# Project6_Circuit_Diagrams_1_1.net
KiCad netlist of a schematic drawn in EasyEDA
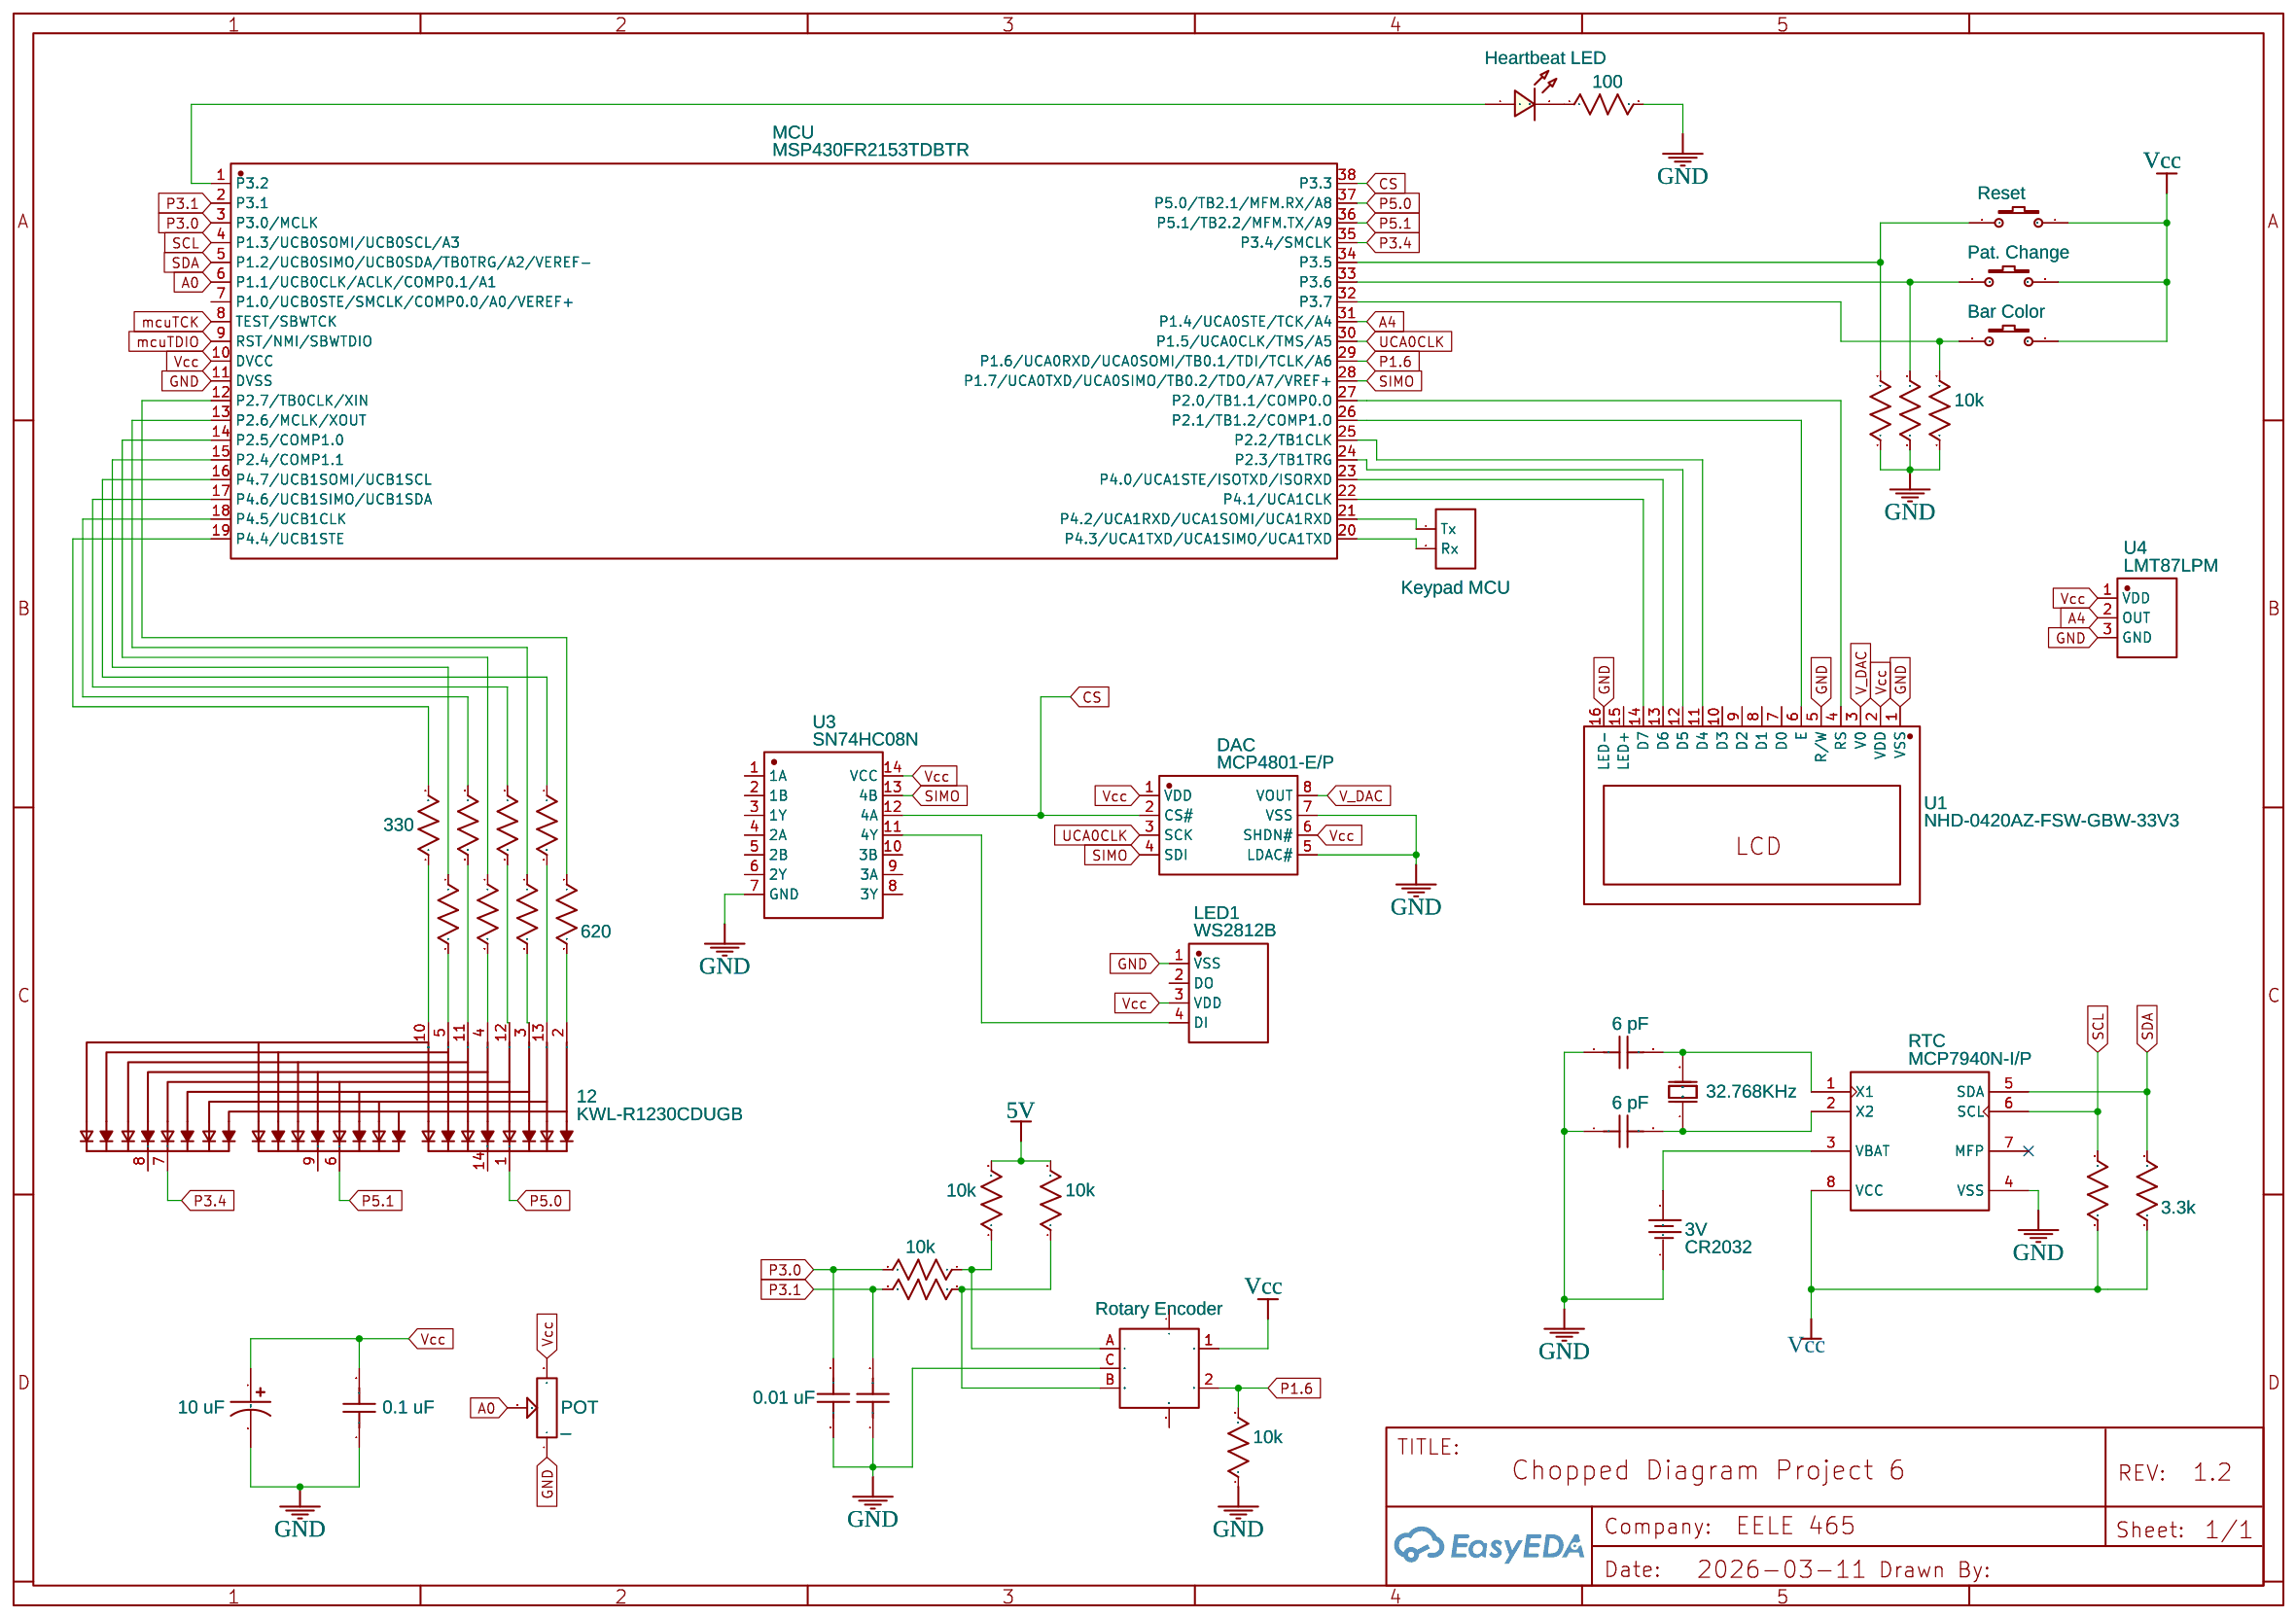
[diagram p0: Main]
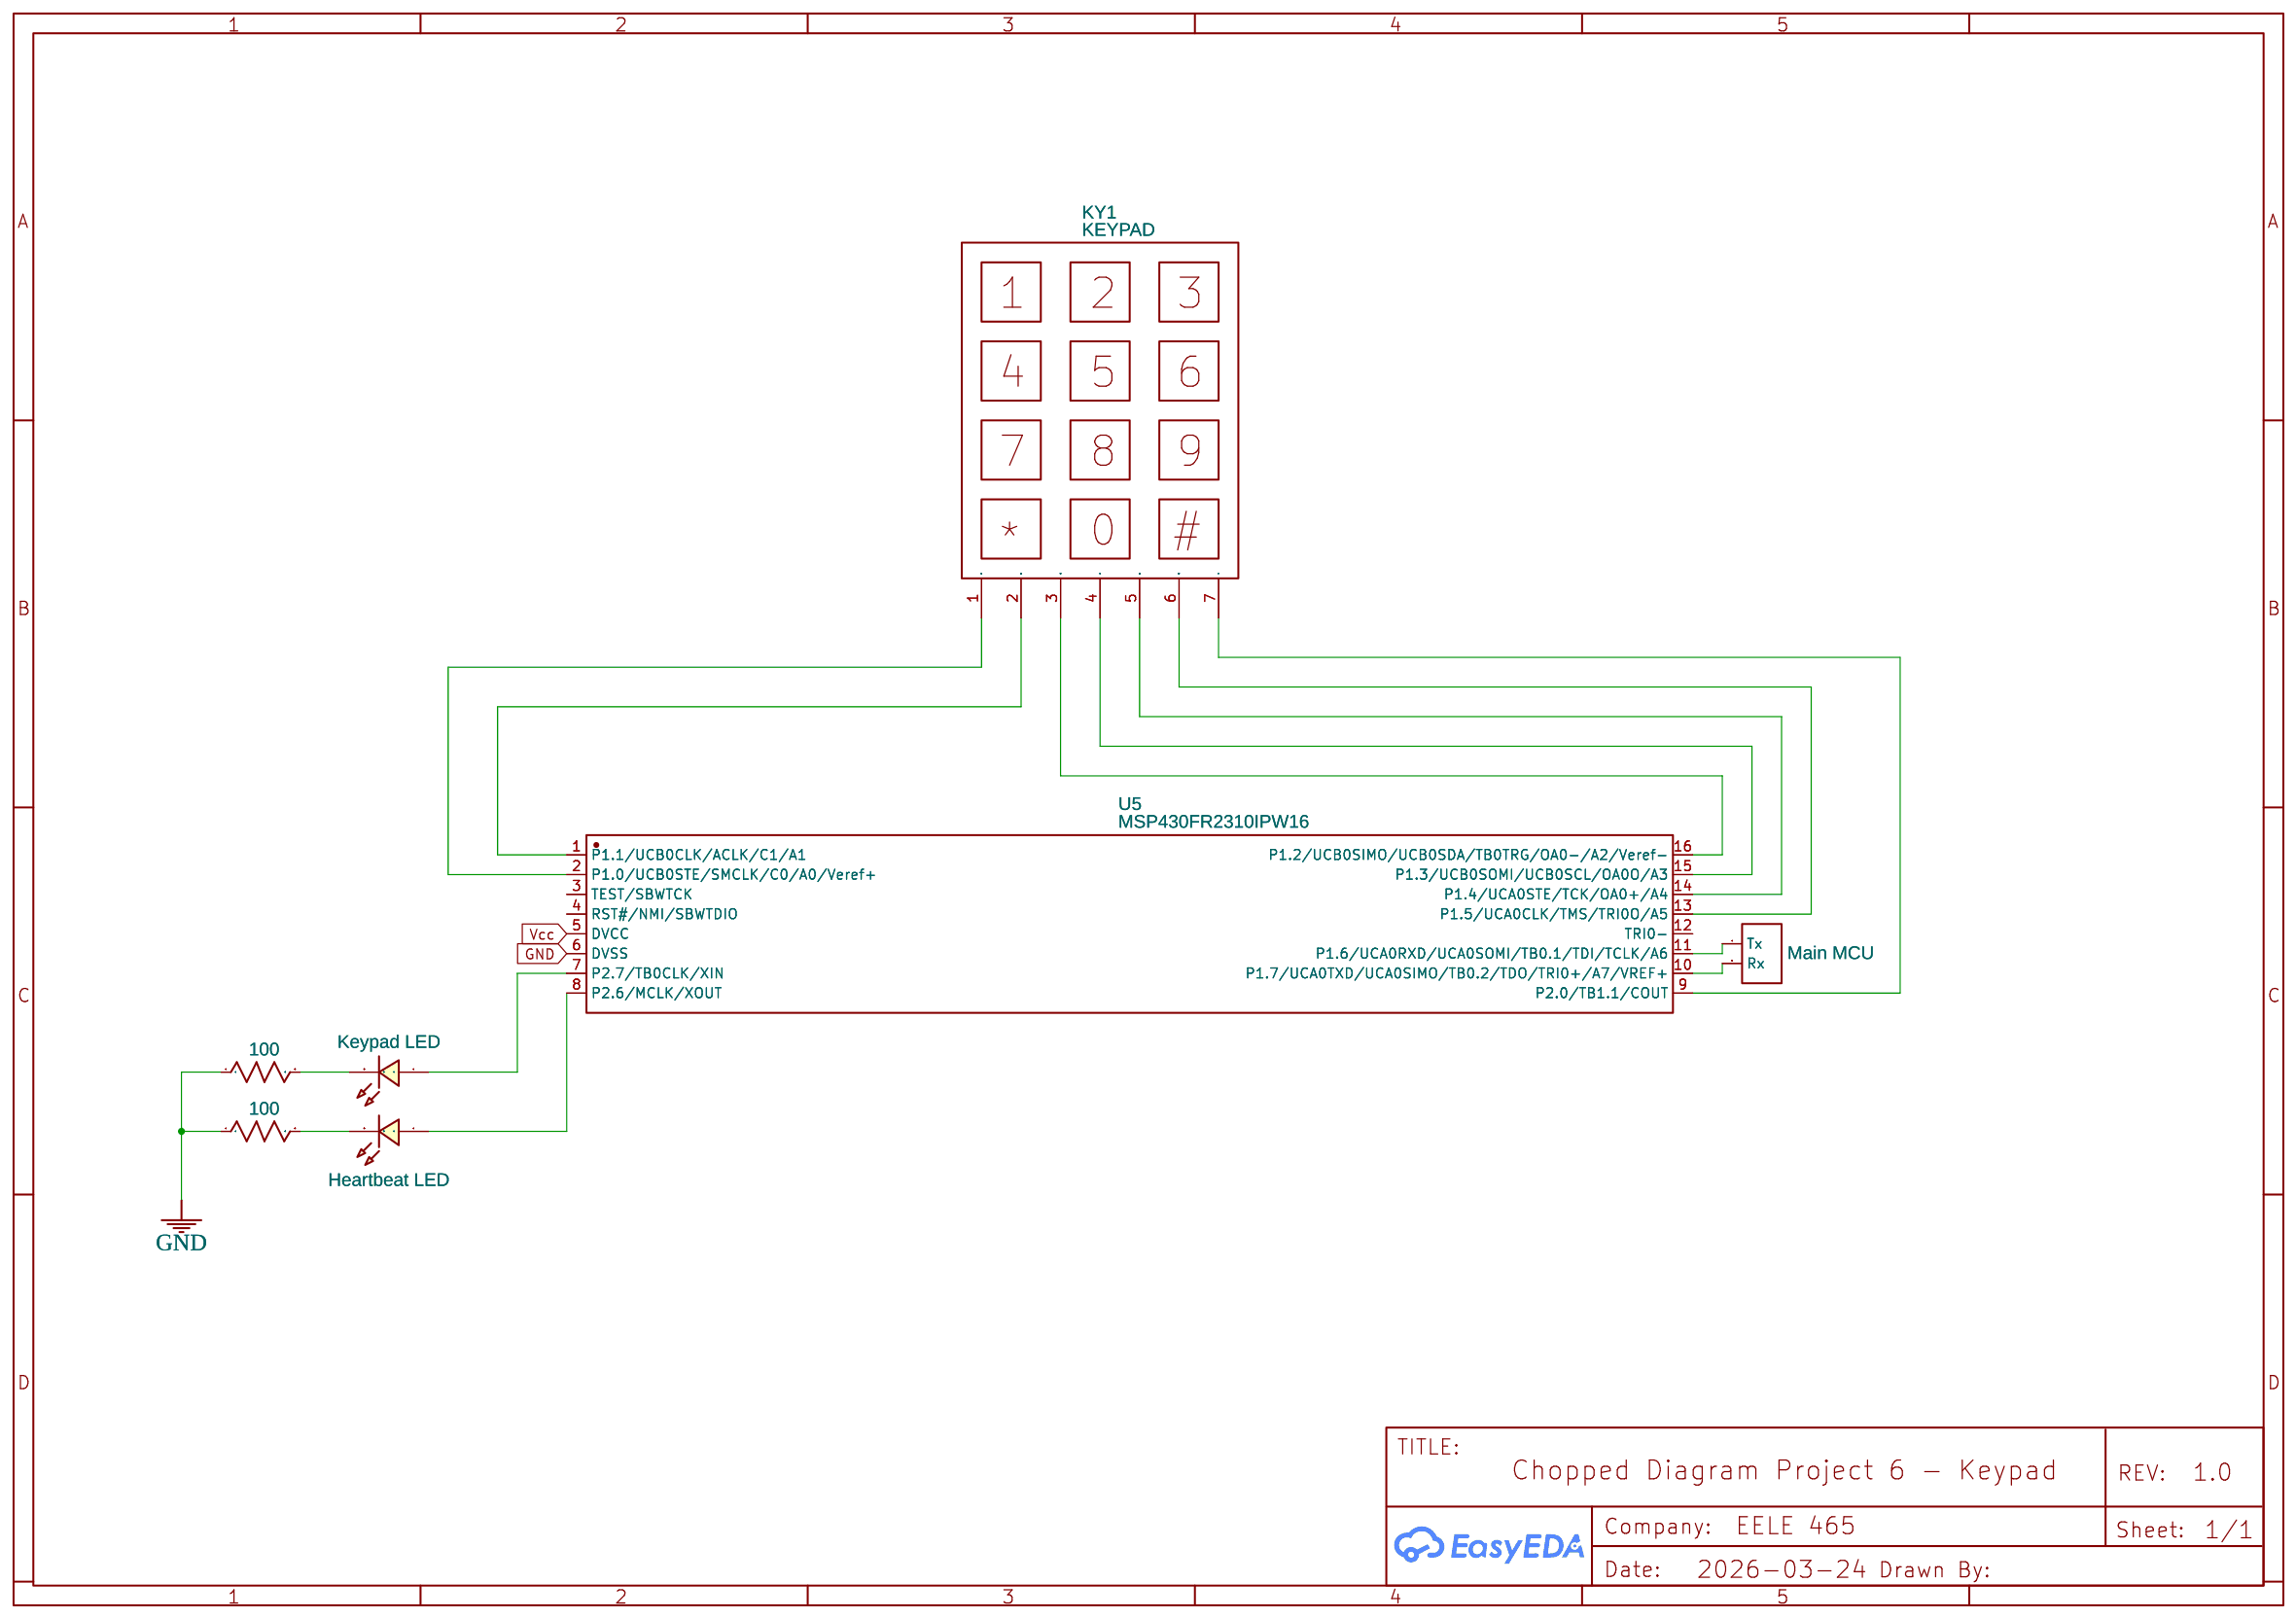
[diagram p1: Keypad]

(export (version "E")
  (design (tool "Eeschema 10.0.6"))
  (components
    (comp (ref "3V")
      (value "CR2032")
      (fields (field (name "Manufacturer Part") "CH25-2032LF") (field (name "Manufacturer") "Multicomp"))
      (libsource (lib "") (part "CH25-2032LF"))
    )
    (comp (ref "12") (value "KWL-R1230CDUGB") (libsource (lib "") (part "KWL-R1230CDUGB")))
    (comp (ref "C1") (value "6 pF") (libsource (lib "") (part "C_0603_US_1")))
    (comp (ref "C2") (value "6 pF") (libsource (lib "") (part "C_0603_US_1")))
    (comp (ref "C3") (value "10 uF") (libsource (lib "") (part "C_Tan_SMD_A_US")))
    (comp (ref "C4") (value "0.1 uF") (libsource (lib "") (part "C_0603_US")))
    (comp (ref "C5") (value "0.01 uF") (libsource (lib "") (part "C_0603_US")))
    (comp (ref "C6") (value "0.01 uF") (libsource (lib "") (part "C_0603_US")))
    (comp (ref "CMD-LINE") (value "Keypad MCU") (libsource (lib "") (part "HDR-F-2.54_1x2")))
    (comp (ref "DAC")
      (value "MCP4801-E/P")
      (fields (field (name "Manufacturer") "MICROCHIP(美国微芯)"))
      (libsource (lib "") (part "MCP4801-E/P"))
    )
    (comp (ref "KEY1")
      (value "Pat. Change")
      (fields (field (name "Manufacturer Part") "K2-1107ST-A4SW-06"))
      (libsource (lib "") (part "K2-3.6×6.1_SMD"))
    )
    (comp (ref "KEY2")
      (value "Reset")
      (fields (field (name "Manufacturer Part") "K2-1107ST-A4SW-06"))
      (libsource (lib "") (part "K2-3.6×6.1_SMD"))
    )
    (comp (ref "KEY3")
      (value "Bar Color")
      (fields (field (name "Manufacturer Part") "K2-1107ST-A4SW-06"))
      (libsource (lib "") (part "K2-3.6×6.1_SMD"))
    )
    (comp (ref "LED1")
      (value "WS2812B")
      (fields (field (name "Manufacturer Part") "WS2812B-4020side-WGYH"))
      (libsource (lib "") (part "WS2812B-4020SIDE-WGYH"))
    )
    (comp (ref "MCU")
      (value "MSP430FR2153TDBTR")
      (fields (field (name "Manufacturer") "TI(德州仪器)"))
      (libsource (lib "") (part "MSP430FR2153TDBTR"))
    )
    (comp (ref "POT") (value "_") (libsource (lib "") (part "SLIDE_POTENTIOMETER_45")))
    (comp (ref "R1") (value "330") (libsource (lib "") (part "R_0603_US")))
    (comp (ref "R2") (value "1k") (libsource (lib "") (part "R_0603_US_2")))
    (comp (ref "R3") (value "1k") (libsource (lib "") (part "R_0603_US_2")))
    (comp (ref "R4") (value "1k") (libsource (lib "") (part "R_0603_US_2")))
    (comp (ref "R5") (value "1k") (libsource (lib "") (part "R_0603_US_2")))
    (comp (ref "R6") (value "1k") (libsource (lib "") (part "R_0603_US_2")))
    (comp (ref "R7") (value "100") (libsource (lib "") (part "R_0603_US_3")))
    (comp (ref "R8") (value "10k") (libsource (lib "") (part "R_0603_US")))
    (comp (ref "R9") (value "330") (libsource (lib "") (part "R_0603_US_2")))
    (comp (ref "R10") (value "620") (libsource (lib "") (part "R_0603_US_2")))
    (comp (ref "R13") (value "10k") (libsource (lib "") (part "R_0603_US")))
    (comp (ref "R14") (value "10k") (libsource (lib "") (part "R_0603_US")))
    (comp (ref "R15") (value "10k") (libsource (lib "") (part "R_0603_US")))
    (comp (ref "R16") (value "10k") (libsource (lib "") (part "R_0603_US")))
    (comp (ref "R17") (value "10k") (libsource (lib "") (part "R_0603_US")))
    (comp (ref "R18") (value "1k") (libsource (lib "") (part "R_0603_US")))
    (comp (ref "R19") (value "3.3k") (libsource (lib "") (part "R_0603_US")))
    (comp (ref "R20") (value "10k") (libsource (lib "") (part "R_0603_US_1")))
    (comp (ref "R21") (value "10k") (libsource (lib "") (part "R_0603_US_1")))
    (comp (ref "RTC")
      (value "MCP7940N-I/P")
      (fields (field (name "Manufacturer") "MICROCHIP(美国微芯)"))
      (libsource (lib "") (part "MCP7940N-I/P"))
    )
    (comp (ref "SC1_ENC")
      (value "Rotary Encoder")
      (fields (field (name "Manufacturer Part") "PEC12R-4130F-S0012") (field (name "Manufacturer") "BOURNS"))
      (libsource (lib "") (part "PEC12R-4130F-S0012"))
    )
    (comp (ref "STATUS1")
      (value "Heartbeat LED")
      (fields
        (field (name "Manufacturer Part") "19-217/GHC-YR1S2/3T")
        (field (name "Manufacturer") "EVERLIGHT(台湾亿光)")
      )
      (libsource (lib "") (part "LED-0603_G"))
    )
    (comp (ref "U1")
      (value "NHD-0420AZ-FSW-GBW-33V3")
      (fields (field (name "Manufacturer") "Newhaven display"))
      (libsource (lib "") (part "NHD-0420AZ-FSW-GBW-33V3"))
    )
    (comp (ref "U3")
      (value "SN74HC08N")
      (fields (field (name "Manufacturer") "TI(德州仪器)"))
      (libsource (lib "") (part "SN74HC08N"))
    )
    (comp (ref "U4")
      (value "LMT87LPM")
      (fields (field (name "Manufacturer") "TI(德州仪器)"))
      (libsource (lib "") (part "LMT87LPM"))
    )
    (comp (ref "X1")
      (value "32.768KHz")
      (fields (field (name "Manufacturer Part") "CFS-20632768EZF"))
      (libsource (lib "") (part "CFS-20632768EZFB"))
    )
    (comp (ref "CMD-LINE1") (value "Main MCU") (libsource (lib "") (part "HDR-F-2.54_1x2")))
    (comp (ref "KY1") (value "KEYPAD") (libsource (lib "") (part "KEYPAD")))
    (comp (ref "R11") (value "100") (libsource (lib "") (part "R_0603_US")))
    (comp (ref "R12") (value "100") (libsource (lib "") (part "R_0603_US")))
    (comp (ref "STATUS2")
      (value "Heartbeat LED")
      (fields
        (field (name "Manufacturer Part") "19-217/GHC-YR1S2/3T")
        (field (name "Manufacturer") "EVERLIGHT(台湾亿光)")
      )
      (libsource (lib "") (part "LED-0603_G"))
    )
    (comp (ref "STATUS3")
      (value "Keypad LED")
      (fields
        (field (name "Manufacturer Part") "19-217/GHC-YR1S2/3T")
        (field (name "Manufacturer") "EVERLIGHT(台湾亿光)")
      )
      (libsource (lib "") (part "LED-0603_G"))
    )
    (comp (ref "U5")
      (value "MSP430FR2310IPW16")
      (fields (field (name "Manufacturer") "TI(德州仪器)"))
      (libsource (lib "") (part "MSP430FR2310IPW16"))
    )
  )
  (nets
    (net (code "1") (name "5V") (class "Default")
      (node (ref "R16") (pin "2") (pinfunction "2_2") (pintype "unspecified"))
      (node (ref "R17") (pin "2") (pinfunction "2_2") (pintype "unspecified"))
    )
    (net (code "2") (name "A0") (class "Default")
      (node (ref "MCU") (pin "6") (pinfunction "P1.1/UCB0CLK/ACLK/COMP0.1/A1_6") (pintype "unspecified"))
      (node (ref "POT") (pin "B") (pinfunction "B_B") (pintype "unspecified"))
    )
    (net (code "3") (name "A4") (class "Default")
      (node (ref "MCU") (pin "31") (pinfunction "P1.4/UCA0STE/TCK/A4_31") (pintype "unspecified"))
      (node (ref "U4") (pin "2") (pinfunction "OUT_2") (pintype "unspecified"))
    )
    (net (code "4") (name "CS") (class "Default")
      (node (ref "DAC") (pin "2") (pinfunction "CS#_2") (pintype "unspecified"))
      (node (ref "MCU") (pin "38") (pinfunction "P3.3_38") (pintype "unspecified"))
      (node (ref "U3") (pin "12") (pinfunction "4A_12") (pintype "unspecified"))
    )
    (net (code "5") (name "GND") (class "Default")
      (node (ref "3V") (pin "1") (pinfunction "1_1") (pintype "input"))
      (node (ref "C1") (pin "1") (pinfunction "1_1") (pintype "unspecified"))
      (node (ref "C2") (pin "1") (pinfunction "1_1") (pintype "unspecified"))
      (node (ref "C3") (pin "2") (pinfunction "2_2") (pintype "unspecified"))
      (node (ref "C4") (pin "1") (pinfunction "1_1") (pintype "unspecified"))
      (node (ref "C5") (pin "1") (pinfunction "1_1") (pintype "unspecified"))
      (node (ref "C6") (pin "1") (pinfunction "1_1") (pintype "unspecified"))
      (node (ref "DAC") (pin "5") (pinfunction "LDAC#_5") (pintype "unspecified"))
      (node (ref "DAC") (pin "7") (pinfunction "VSS_7") (pintype "unspecified"))
      (node (ref "LED1") (pin "1") (pinfunction "VSS_1") (pintype "unspecified"))
      (node (ref "MCU") (pin "11") (pinfunction "DVSS_11") (pintype "unspecified"))
      (node (ref "POT") (pin "A") (pinfunction "A_A") (pintype "unspecified"))
      (node (ref "R11") (pin "1") (pinfunction "1_1") (pintype "unspecified"))
      (node (ref "R12") (pin "1") (pinfunction "1_1") (pintype "unspecified"))
      (node (ref "R13") (pin "1") (pinfunction "1_1") (pintype "unspecified"))
      (node (ref "R14") (pin "1") (pinfunction "1_1") (pintype "unspecified"))
      (node (ref "R15") (pin "1") (pinfunction "1_1") (pintype "unspecified"))
      (node (ref "R7") (pin "2") (pinfunction "2_2") (pintype "unspecified"))
      (node (ref "R8") (pin "1") (pinfunction "1_1") (pintype "unspecified"))
      (node (ref "RTC") (pin "4") (pinfunction "VSS_4") (pintype "passive"))
      (node (ref "SC1_ENC") (pin "C") (pinfunction "C_C") (pintype "unspecified"))
      (node (ref "U1") (pin "1") (pinfunction "VSS_1") (pintype "unspecified"))
      (node (ref "U1") (pin "16") (pinfunction "LED-_16") (pintype "unspecified"))
      (node (ref "U1") (pin "5") (pinfunction "R/W_5") (pintype "unspecified"))
      (node (ref "U3") (pin "7") (pinfunction "GND_7") (pintype "unspecified"))
      (node (ref "U4") (pin "3") (pinfunction "GND_3") (pintype "unspecified"))
      (node (ref "U5") (pin "6") (pinfunction "DVSS_6") (pintype "unspecified"))
    )
    (net (code "6") (name "Net-(12-Pad2)") (class "Default")
      (node (ref "12") (pin "2") (pinfunction "2_2") (pintype "unspecified"))
      (node (ref "R10") (pin "2") (pinfunction "2_2") (pintype "unspecified"))
    )
    (net (code "7") (name "Net-(12-Pad3)") (class "Default")
      (node (ref "12") (pin "3") (pinfunction "3_3") (pintype "unspecified"))
      (node (ref "R6") (pin "2") (pinfunction "2_2") (pintype "unspecified"))
    )
    (net (code "8") (name "Net-(12-Pad4)") (class "Default")
      (node (ref "12") (pin "4") (pinfunction "4_4") (pintype "unspecified"))
      (node (ref "R4") (pin "2") (pinfunction "2_2") (pintype "unspecified"))
    )
    (net (code "9") (name "Net-(12-Pad5)") (class "Default")
      (node (ref "12") (pin "5") (pinfunction "5_5") (pintype "unspecified"))
      (node (ref "R2") (pin "2") (pinfunction "2_2") (pintype "unspecified"))
    )
    (net (code "10") (name "Net-(12-Pad10)") (class "Default")
      (node (ref "12") (pin "10") (pinfunction "10_10") (pintype "unspecified"))
      (node (ref "R1") (pin "1") (pinfunction "1_1") (pintype "unspecified"))
    )
    (net (code "11") (name "Net-(12-Pad11)") (class "Default")
      (node (ref "12") (pin "11") (pinfunction "11_11") (pintype "unspecified"))
      (node (ref "R3") (pin "2") (pinfunction "2_2") (pintype "unspecified"))
    )
    (net (code "12") (name "Net-(12-Pad12)") (class "Default")
      (node (ref "12") (pin "12") (pinfunction "12_12") (pintype "unspecified"))
      (node (ref "R5") (pin "2") (pinfunction "2_2") (pintype "unspecified"))
    )
    (net (code "13") (name "Net-(12-Pad13)") (class "Default")
      (node (ref "12") (pin "13") (pinfunction "13_13") (pintype "unspecified"))
      (node (ref "R9") (pin "2") (pinfunction "2_2") (pintype "unspecified"))
    )
    (net (code "14") (name "Net-(CMD-LINE-Rx)") (class "Default")
      (node (ref "CMD-LINE") (pin "2") (pinfunction "Rx_2") (pintype "input"))
      (node (ref "MCU") (pin "20") (pinfunction "P4.3/UCA1TXD/UCA1SIMO/UCA1TXD_20") (pintype "unspecified"))
    )
    (net (code "15") (name "Net-(CMD-LINE-Tx)") (class "Default")
      (node (ref "CMD-LINE") (pin "1") (pinfunction "Tx_1") (pintype "input"))
      (node (ref "MCU") (pin "21") (pinfunction "P4.2/UCA1RXD/UCA1SOMI/UCA1RXD_21") (pintype "unspecified"))
    )
    (net (code "16") (name "Net-(CMD-LINE1-Rx)") (class "Default")
      (node (ref "CMD-LINE1") (pin "2") (pinfunction "Rx_2") (pintype "input"))
      (node (ref "U5") (pin "10") (pinfunction "P1.7/UCA0TXD/UCA0SIMO/TB0.2/TDO/TRI0+/A7/VREF+_10") (pintype "unspecified"))
    )
    (net (code "17") (name "Net-(CMD-LINE1-Tx)") (class "Default")
      (node (ref "CMD-LINE1") (pin "1") (pinfunction "Tx_1") (pintype "input"))
      (node (ref "U5") (pin "11") (pinfunction "P1.6/UCA0RXD/UCA0SOMI/TB0.1/TDI/TCLK/A6_11") (pintype "unspecified"))
    )
    (net (code "18") (name "Net-(LED1-DI)") (class "Default")
      (node (ref "LED1") (pin "4") (pinfunction "DI_4") (pintype "unspecified"))
      (node (ref "U3") (pin "11") (pinfunction "4Y_11") (pintype "unspecified"))
    )
    (net (code "19") (name "Net-(MCU-P2.0{slash}TB1.1{slash}COMP0.O)") (class "Default")
      (node (ref "MCU") (pin "27") (pinfunction "P2.0/TB1.1/COMP0.O_27") (pintype "unspecified"))
      (node (ref "U1") (pin "4") (pinfunction "RS_4") (pintype "unspecified"))
    )
    (net (code "20") (name "Net-(MCU-P2.1{slash}TB1.2{slash}COMP1.O)") (class "Default")
      (node (ref "MCU") (pin "26") (pinfunction "P2.1/TB1.2/COMP1.O_26") (pintype "unspecified"))
      (node (ref "U1") (pin "6") (pinfunction "E_6") (pintype "unspecified"))
    )
    (net (code "21") (name "Net-(MCU-P2.2{slash}TB1CLK)") (class "Default")
      (node (ref "MCU") (pin "25") (pinfunction "P2.2/TB1CLK_25") (pintype "unspecified"))
      (node (ref "U1") (pin "11") (pinfunction "D4_11") (pintype "unspecified"))
    )
    (net (code "22") (name "Net-(MCU-P2.3{slash}TB1TRG)") (class "Default")
      (node (ref "MCU") (pin "24") (pinfunction "P2.3/TB1TRG_24") (pintype "unspecified"))
      (node (ref "U1") (pin "12") (pinfunction "D5_12") (pintype "unspecified"))
    )
    (net (code "23") (name "Net-(MCU-P2.4{slash}COMP1.1)") (class "Default")
      (node (ref "MCU") (pin "15") (pinfunction "P2.4/COMP1.1_15") (pintype "unspecified"))
      (node (ref "R2") (pin "1") (pinfunction "1_1") (pintype "unspecified"))
    )
    (net (code "24") (name "Net-(MCU-P2.5{slash}COMP1.0)") (class "Default")
      (node (ref "MCU") (pin "14") (pinfunction "P2.5/COMP1.0_14") (pintype "unspecified"))
      (node (ref "R4") (pin "1") (pinfunction "1_1") (pintype "unspecified"))
    )
    (net (code "25") (name "Net-(MCU-P2.6{slash}MCLK{slash}XOUT)") (class "Default")
      (node (ref "MCU") (pin "13") (pinfunction "P2.6/MCLK/XOUT_13") (pintype "unspecified"))
      (node (ref "R6") (pin "1") (pinfunction "1_1") (pintype "unspecified"))
    )
    (net (code "26") (name "Net-(MCU-P2.7{slash}TB0CLK{slash}XIN)") (class "Default")
      (node (ref "MCU") (pin "12") (pinfunction "P2.7/TB0CLK/XIN_12") (pintype "unspecified"))
      (node (ref "R10") (pin "1") (pinfunction "1_1") (pintype "unspecified"))
    )
    (net (code "27") (name "Net-(MCU-P3.2)") (class "Default")
      (node (ref "MCU") (pin "1") (pinfunction "P3.2_1") (pintype "unspecified"))
      (node (ref "STATUS1") (pin "1") (pinfunction "1_1") (pintype "unspecified"))
    )
    (net (code "28") (name "Net-(MCU-P3.5)") (class "Default")
      (node (ref "KEY2") (pin "1") (pinfunction "1_1") (pintype "unspecified"))
      (node (ref "MCU") (pin "34") (pinfunction "P3.5_34") (pintype "unspecified"))
      (node (ref "R14") (pin "2") (pinfunction "2_2") (pintype "unspecified"))
    )
    (net (code "29") (name "Net-(MCU-P3.6)") (class "Default")
      (node (ref "KEY1") (pin "1") (pinfunction "1_1") (pintype "unspecified"))
      (node (ref "MCU") (pin "33") (pinfunction "P3.6_33") (pintype "unspecified"))
      (node (ref "R13") (pin "2") (pinfunction "2_2") (pintype "unspecified"))
    )
    (net (code "30") (name "Net-(MCU-P3.7)") (class "Default")
      (node (ref "KEY3") (pin "1") (pinfunction "1_1") (pintype "unspecified"))
      (node (ref "MCU") (pin "32") (pinfunction "P3.7_32") (pintype "unspecified"))
      (node (ref "R8") (pin "2") (pinfunction "2_2") (pintype "unspecified"))
    )
    (net (code "31") (name "Net-(MCU-P4.0{slash}UCA1STE{slash}ISOTXD{slash}ISORXD)") (class "Default")
      (node (ref "MCU") (pin "23") (pinfunction "P4.0/UCA1STE/ISOTXD/ISORXD_23") (pintype "unspecified"))
      (node (ref "U1") (pin "13") (pinfunction "D6_13") (pintype "unspecified"))
    )
    (net (code "32") (name "Net-(MCU-P4.1{slash}UCA1CLK)") (class "Default")
      (node (ref "MCU") (pin "22") (pinfunction "P4.1/UCA1CLK_22") (pintype "unspecified"))
      (node (ref "U1") (pin "14") (pinfunction "D7_14") (pintype "unspecified"))
    )
    (net (code "33") (name "Net-(MCU-P4.4{slash}UCB1STE)") (class "Default")
      (node (ref "MCU") (pin "19") (pinfunction "P4.4/UCB1STE_19") (pintype "unspecified"))
      (node (ref "R1") (pin "2") (pinfunction "2_2") (pintype "unspecified"))
    )
    (net (code "34") (name "Net-(MCU-P4.5{slash}UCB1CLK)") (class "Default")
      (node (ref "MCU") (pin "18") (pinfunction "P4.5/UCB1CLK_18") (pintype "unspecified"))
      (node (ref "R3") (pin "1") (pinfunction "1_1") (pintype "unspecified"))
    )
    (net (code "35") (name "Net-(MCU-P4.6{slash}UCB1SIMO{slash}UCB1SDA)") (class "Default")
      (node (ref "MCU") (pin "17") (pinfunction "P4.6/UCB1SIMO/UCB1SDA_17") (pintype "unspecified"))
      (node (ref "R5") (pin "1") (pinfunction "1_1") (pintype "unspecified"))
    )
    (net (code "36") (name "Net-(MCU-P4.7{slash}UCB1SOMI{slash}UCB1SCL)") (class "Default")
      (node (ref "MCU") (pin "16") (pinfunction "P4.7/UCB1SOMI/UCB1SCL_16") (pintype "unspecified"))
      (node (ref "R9") (pin "1") (pinfunction "1_1") (pintype "unspecified"))
    )
    (net (code "37") (name "Net-(R7-Pad1)") (class "Default")
      (node (ref "R7") (pin "1") (pinfunction "1_1") (pintype "unspecified"))
      (node (ref "STATUS1") (pin "2") (pinfunction "2_2") (pintype "unspecified"))
    )
    (net (code "38") (name "Net-(R11-Pad2)") (class "Default")
      (node (ref "R11") (pin "2") (pinfunction "2_2") (pintype "unspecified"))
      (node (ref "STATUS3") (pin "2") (pinfunction "2_2") (pintype "unspecified"))
    )
    (net (code "39") (name "Net-(R12-Pad2)") (class "Default")
      (node (ref "R12") (pin "2") (pinfunction "2_2") (pintype "unspecified"))
      (node (ref "STATUS2") (pin "2") (pinfunction "2_2") (pintype "unspecified"))
    )
    (net (code "40") (name "Net-(R16-Pad1)") (class "Default")
      (node (ref "R16") (pin "1") (pinfunction "1_1") (pintype "unspecified"))
      (node (ref "R20") (pin "1") (pinfunction "1_1") (pintype "unspecified"))
      (node (ref "SC1_ENC") (pin "A") (pinfunction "A_A") (pintype "unspecified"))
    )
    (net (code "41") (name "Net-(R17-Pad1)") (class "Default")
      (node (ref "R17") (pin "1") (pinfunction "1_1") (pintype "unspecified"))
      (node (ref "R21") (pin "1") (pinfunction "1_1") (pintype "unspecified"))
      (node (ref "SC1_ENC") (pin "B") (pinfunction "B_B") (pintype "unspecified"))
    )
    (net (code "42") (name "Net-(RTC-VBAT)") (class "Default")
      (node (ref "3V") (pin "2") (pinfunction "2_2") (pintype "input"))
      (node (ref "RTC") (pin "3") (pinfunction "VBAT_3") (pintype "passive"))
    )
    (net (code "43") (name "Net-(RTC-X1)") (class "Default")
      (node (ref "C1") (pin "2") (pinfunction "2_2") (pintype "unspecified"))
      (node (ref "RTC") (pin "1") (pinfunction "X1_1") (pintype "unspecified"))
      (node (ref "X1") (pin "2") (pinfunction "OSC2_2") (pintype "input"))
    )
    (net (code "44") (name "Net-(RTC-X2)") (class "Default")
      (node (ref "C2") (pin "2") (pinfunction "2_2") (pintype "unspecified"))
      (node (ref "RTC") (pin "2") (pinfunction "X2_2") (pintype "output"))
      (node (ref "X1") (pin "1") (pinfunction "OSC1_1") (pintype "input"))
    )
    (net (code "45") (name "Net-(U5-P1.0{slash}UCB0STE{slash}SMCLK{slash}C0{slash}A0{slash}Veref+)") (class "Default")
      (node (ref "KY1") (pin "1") (pinfunction "1_1") (pintype "unspecified"))
      (node (ref "U5") (pin "2") (pinfunction "P1.0/UCB0STE/SMCLK/C0/A0/Veref+_2") (pintype "unspecified"))
    )
    (net (code "46") (name "Net-(U5-P1.1{slash}UCB0CLK{slash}ACLK{slash}C1{slash}A1)") (class "Default")
      (node (ref "KY1") (pin "2") (pinfunction "2_2") (pintype "unspecified"))
      (node (ref "U5") (pin "1") (pinfunction "P1.1/UCB0CLK/ACLK/C1/A1_1") (pintype "unspecified"))
    )
    (net (code "47") (name "Net-(U5-P1.2{slash}UCB0SIMO{slash}UCB0SDA{slash}TB0TRG{slash}OA0-{slash}A2{slash}Veref-)") (class "Default")
      (node (ref "KY1") (pin "3") (pinfunction "3_3") (pintype "unspecified"))
      (node (ref "U5") (pin "16") (pinfunction "P1.2/UCB0SIMO/UCB0SDA/TB0TRG/OA0-/A2/Veref-_16") (pintype "unspecified"))
    )
    (net (code "48") (name "Net-(U5-P1.3{slash}UCB0SOMI{slash}UCB0SCL{slash}OA0O{slash}A3)") (class "Default")
      (node (ref "KY1") (pin "4") (pinfunction "4_4") (pintype "unspecified"))
      (node (ref "U5") (pin "15") (pinfunction "P1.3/UCB0SOMI/UCB0SCL/OA0O/A3_15") (pintype "unspecified"))
    )
    (net (code "49") (name "Net-(U5-P1.4{slash}UCA0STE{slash}TCK{slash}OA0+{slash}A4)") (class "Default")
      (node (ref "KY1") (pin "5") (pinfunction "5_5") (pintype "unspecified"))
      (node (ref "U5") (pin "14") (pinfunction "P1.4/UCA0STE/TCK/OA0+/A4_14") (pintype "unspecified"))
    )
    (net (code "50") (name "Net-(U5-P1.5{slash}UCA0CLK{slash}TMS{slash}TRI0O{slash}A5)") (class "Default")
      (node (ref "KY1") (pin "6") (pinfunction "6_6") (pintype "unspecified"))
      (node (ref "U5") (pin "13") (pinfunction "P1.5/UCA0CLK/TMS/TRI0O/A5_13") (pintype "unspecified"))
    )
    (net (code "51") (name "Net-(U5-P2.0{slash}TB1.1{slash}COUT)") (class "Default")
      (node (ref "KY1") (pin "7") (pinfunction "7_7") (pintype "unspecified"))
      (node (ref "U5") (pin "9") (pinfunction "P2.0/TB1.1/COUT_9") (pintype "unspecified"))
    )
    (net (code "52") (name "Net-(U5-P2.6{slash}MCLK{slash}XOUT)") (class "Default")
      (node (ref "STATUS2") (pin "1") (pinfunction "1_1") (pintype "unspecified"))
      (node (ref "U5") (pin "8") (pinfunction "P2.6/MCLK/XOUT_8") (pintype "unspecified"))
    )
    (net (code "53") (name "Net-(U5-P2.7{slash}TB0CLK{slash}XIN)") (class "Default")
      (node (ref "STATUS3") (pin "1") (pinfunction "1_1") (pintype "unspecified"))
      (node (ref "U5") (pin "7") (pinfunction "P2.7/TB0CLK/XIN_7") (pintype "unspecified"))
    )
    (net (code "54") (name "P1.6") (class "Default")
      (node (ref "MCU") (pin "29") (pinfunction "P1.6/UCA0RXD/UCA0SOMI/TB0.1/TDI/TCLK/A6_29") (pintype "unspecified"))
      (node (ref "R15") (pin "2") (pinfunction "2_2") (pintype "unspecified"))
      (node (ref "SC1_ENC") (pin "2") (pinfunction "2_2") (pintype "unspecified"))
    )
    (net (code "55") (name "P3.0") (class "Default")
      (node (ref "C5") (pin "2") (pinfunction "2_2") (pintype "unspecified"))
      (node (ref "MCU") (pin "3") (pinfunction "P3.0/MCLK_3") (pintype "unspecified"))
      (node (ref "R20") (pin "2") (pinfunction "2_2") (pintype "unspecified"))
    )
    (net (code "56") (name "P3.1") (class "Default")
      (node (ref "C6") (pin "2") (pinfunction "2_2") (pintype "unspecified"))
      (node (ref "MCU") (pin "2") (pinfunction "P3.1_2") (pintype "unspecified"))
      (node (ref "R21") (pin "2") (pinfunction "2_2") (pintype "unspecified"))
    )
    (net (code "57") (name "P3.4") (class "Default")
      (node (ref "12") (pin "7") (pinfunction "7_7") (pintype "unspecified"))
      (node (ref "MCU") (pin "35") (pinfunction "P3.4/SMCLK_35") (pintype "unspecified"))
    )
    (net (code "58") (name "P5.0") (class "Default")
      (node (ref "12") (pin "1") (pinfunction "1_1") (pintype "unspecified"))
      (node (ref "MCU") (pin "37") (pinfunction "P5.0/TB2.1/MFM.RX/A8_37") (pintype "unspecified"))
    )
    (net (code "59") (name "P5.1") (class "Default")
      (node (ref "12") (pin "6") (pinfunction "6_6") (pintype "unspecified"))
      (node (ref "MCU") (pin "36") (pinfunction "P5.1/TB2.2/MFM.TX/A9_36") (pintype "unspecified"))
    )
    (net (code "60") (name "SCL") (class "Default")
      (node (ref "MCU") (pin "4") (pinfunction "P1.3/UCB0SOMI/UCB0SCL/A3_4") (pintype "unspecified"))
      (node (ref "R18") (pin "2") (pinfunction "2_2") (pintype "unspecified"))
      (node (ref "RTC") (pin "6") (pinfunction "SCL_6") (pintype "unspecified"))
    )
    (net (code "61") (name "SDA") (class "Default")
      (node (ref "MCU") (pin "5") (pinfunction "P1.2/UCB0SIMO/UCB0SDA/TB0TRG/A2/VEREF-_5") (pintype "unspecified"))
      (node (ref "R19") (pin "2") (pinfunction "2_2") (pintype "unspecified"))
      (node (ref "RTC") (pin "5") (pinfunction "SDA_5") (pintype "bidirectional"))
    )
    (net (code "62") (name "SIMO") (class "Default")
      (node (ref "DAC") (pin "4") (pinfunction "SDI_4") (pintype "unspecified"))
      (node (ref "MCU") (pin "28") (pinfunction "P1.7/UCA0TXD/UCA0SIMO/TB0.2/TDO/A7/VREF+_28") (pintype "unspecified"))
      (node (ref "U3") (pin "13") (pinfunction "4B_13") (pintype "unspecified"))
    )
    (net (code "63") (name "UCA0CLK") (class "Default")
      (node (ref "DAC") (pin "3") (pinfunction "SCK_3") (pintype "unspecified"))
      (node (ref "MCU") (pin "30") (pinfunction "P1.5/UCA0CLK/TMS/A5_30") (pintype "unspecified"))
    )
    (net (code "64") (name "V_DAC") (class "Default")
      (node (ref "DAC") (pin "8") (pinfunction "VOUT_8") (pintype "unspecified"))
      (node (ref "U1") (pin "3") (pinfunction "V0_3") (pintype "unspecified"))
    )
    (net (code "65") (name "Vcc") (class "Default")
      (node (ref "C3") (pin "1") (pinfunction "1_1") (pintype "unspecified"))
      (node (ref "C4") (pin "2") (pinfunction "2_2") (pintype "unspecified"))
      (node (ref "DAC") (pin "1") (pinfunction "VDD_1") (pintype "unspecified"))
      (node (ref "DAC") (pin "6") (pinfunction "SHDN#_6") (pintype "unspecified"))
      (node (ref "KEY1") (pin "2") (pinfunction "2_2") (pintype "unspecified"))
      (node (ref "KEY2") (pin "2") (pinfunction "2_2") (pintype "unspecified"))
      (node (ref "KEY3") (pin "2") (pinfunction "2_2") (pintype "unspecified"))
      (node (ref "LED1") (pin "3") (pinfunction "VDD_3") (pintype "unspecified"))
      (node (ref "MCU") (pin "10") (pinfunction "DVCC_10") (pintype "unspecified"))
      (node (ref "POT") (pin "D") (pinfunction "C_D") (pintype "unspecified"))
      (node (ref "R18") (pin "1") (pinfunction "1_1") (pintype "unspecified"))
      (node (ref "R19") (pin "1") (pinfunction "1_1") (pintype "unspecified"))
      (node (ref "RTC") (pin "8") (pinfunction "VCC_8") (pintype "passive"))
      (node (ref "SC1_ENC") (pin "1") (pinfunction "1_1") (pintype "unspecified"))
      (node (ref "U1") (pin "2") (pinfunction "VDD_2") (pintype "unspecified"))
      (node (ref "U3") (pin "14") (pinfunction "VCC_14") (pintype "unspecified"))
      (node (ref "U4") (pin "1") (pinfunction "VDD_1") (pintype "unspecified"))
      (node (ref "U5") (pin "5") (pinfunction "DVCC_5") (pintype "unspecified"))
    )
    (net (code "66") (name "mcuTCK") (class "Default")
      (node (ref "MCU") (pin "8") (pinfunction "TEST/SBWTCK_8") (pintype "unspecified"))
    )
    (net (code "67") (name "mcuTDIO") (class "Default")
      (node (ref "MCU") (pin "9") (pinfunction "RST/NMI/SBWTDIO_9") (pintype "unspecified"))
    )
    (net (code "68") (name "unconnected-(12-Pad8)") (class "Default")
      (node (ref "12") (pin "8") (pinfunction "8_8") (pintype "unspecified"))
    )
    (net (code "69") (name "unconnected-(12-Pad9)") (class "Default")
      (node (ref "12") (pin "9") (pinfunction "9_9") (pintype "unspecified"))
    )
    (net (code "70") (name "unconnected-(12-Pad14)") (class "Default")
      (node (ref "12") (pin "14") (pinfunction "14_14") (pintype "unspecified"))
    )
    (net (code "71") (name "unconnected-(LED1-DO-Pad2)") (class "Default")
      (node (ref "LED1") (pin "2") (pinfunction "DO_2") (pintype "unspecified"))
    )
    (net (code "72") (name "unconnected-(MCU-P1.0{slash}UCB0STE{slash}SMCLK{slash}COMP0.0{slash}A0{slash}VEREF+-Pad7)") (class "Default")
      (node (ref "MCU") (pin "7") (pinfunction "P1.0/UCB0STE/SMCLK/COMP0.0/A0/VEREF+_7") (pintype "unspecified"))
    )
    (net (code "73") (name "unconnected-(RTC-MFP-Pad7)") (class "Default")
      (node (ref "RTC") (pin "7") (pinfunction "MFP_7") (pintype "unspecified+no_connect"))
    )
    (net (code "74") (name "unconnected-(SC1_ENC-Pad3)") (class "Default")
      (node (ref "SC1_ENC") (pin "3") (pinfunction "3_3") (pintype "unspecified"))
    )
    (net (code "75") (name "unconnected-(SC1_ENC-Pad4)") (class "Default")
      (node (ref "SC1_ENC") (pin "4") (pinfunction "4_4") (pintype "unspecified"))
    )
    (net (code "76") (name "unconnected-(U1-D0-Pad7)") (class "Default")
      (node (ref "U1") (pin "7") (pinfunction "D0_7") (pintype "unspecified"))
    )
    (net (code "77") (name "unconnected-(U1-D1-Pad8)") (class "Default")
      (node (ref "U1") (pin "8") (pinfunction "D1_8") (pintype "unspecified"))
    )
    (net (code "78") (name "unconnected-(U1-D2-Pad9)") (class "Default")
      (node (ref "U1") (pin "9") (pinfunction "D2_9") (pintype "unspecified"))
    )
    (net (code "79") (name "unconnected-(U1-D3-Pad10)") (class "Default")
      (node (ref "U1") (pin "10") (pinfunction "D3_10") (pintype "unspecified"))
    )
    (net (code "80") (name "unconnected-(U1-LED+-Pad15)") (class "Default")
      (node (ref "U1") (pin "15") (pinfunction "LED+_15") (pintype "unspecified"))
    )
    (net (code "81") (name "unconnected-(U3-1A-Pad1)") (class "Default")
      (node (ref "U3") (pin "1") (pinfunction "1A_1") (pintype "unspecified"))
    )
    (net (code "82") (name "unconnected-(U3-1B-Pad2)") (class "Default")
      (node (ref "U3") (pin "2") (pinfunction "1B_2") (pintype "unspecified"))
    )
    (net (code "83") (name "unconnected-(U3-1Y-Pad3)") (class "Default")
      (node (ref "U3") (pin "3") (pinfunction "1Y_3") (pintype "unspecified"))
    )
    (net (code "84") (name "unconnected-(U3-2A-Pad4)") (class "Default")
      (node (ref "U3") (pin "4") (pinfunction "2A_4") (pintype "unspecified"))
    )
    (net (code "85") (name "unconnected-(U3-2B-Pad5)") (class "Default")
      (node (ref "U3") (pin "5") (pinfunction "2B_5") (pintype "unspecified"))
    )
    (net (code "86") (name "unconnected-(U3-2Y-Pad6)") (class "Default")
      (node (ref "U3") (pin "6") (pinfunction "2Y_6") (pintype "unspecified"))
    )
    (net (code "87") (name "unconnected-(U3-3A-Pad9)") (class "Default")
      (node (ref "U3") (pin "9") (pinfunction "3A_9") (pintype "unspecified"))
    )
    (net (code "88") (name "unconnected-(U3-3B-Pad10)") (class "Default")
      (node (ref "U3") (pin "10") (pinfunction "3B_10") (pintype "unspecified"))
    )
    (net (code "89") (name "unconnected-(U3-3Y-Pad8)") (class "Default")
      (node (ref "U3") (pin "8") (pinfunction "3Y_8") (pintype "unspecified"))
    )
    (net (code "90") (name "unconnected-(U5-RST#{slash}NMI{slash}SBWTDIO-Pad4)") (class "Default")
      (node (ref "U5") (pin "4") (pinfunction "RST#/NMI/SBWTDIO_4") (pintype "unspecified"))
    )
    (net (code "91") (name "unconnected-(U5-TEST{slash}SBWTCK-Pad3)") (class "Default")
      (node (ref "U5") (pin "3") (pinfunction "TEST/SBWTCK_3") (pintype "unspecified"))
    )
    (net (code "92") (name "unconnected-(U5-TRI0--Pad12)") (class "Default")
      (node (ref "U5") (pin "12") (pinfunction "TRI0-_12") (pintype "unspecified"))
    )
  )
)
